# usbpsu2.net
KiCad netlist of a schematic drawn in EAGLE
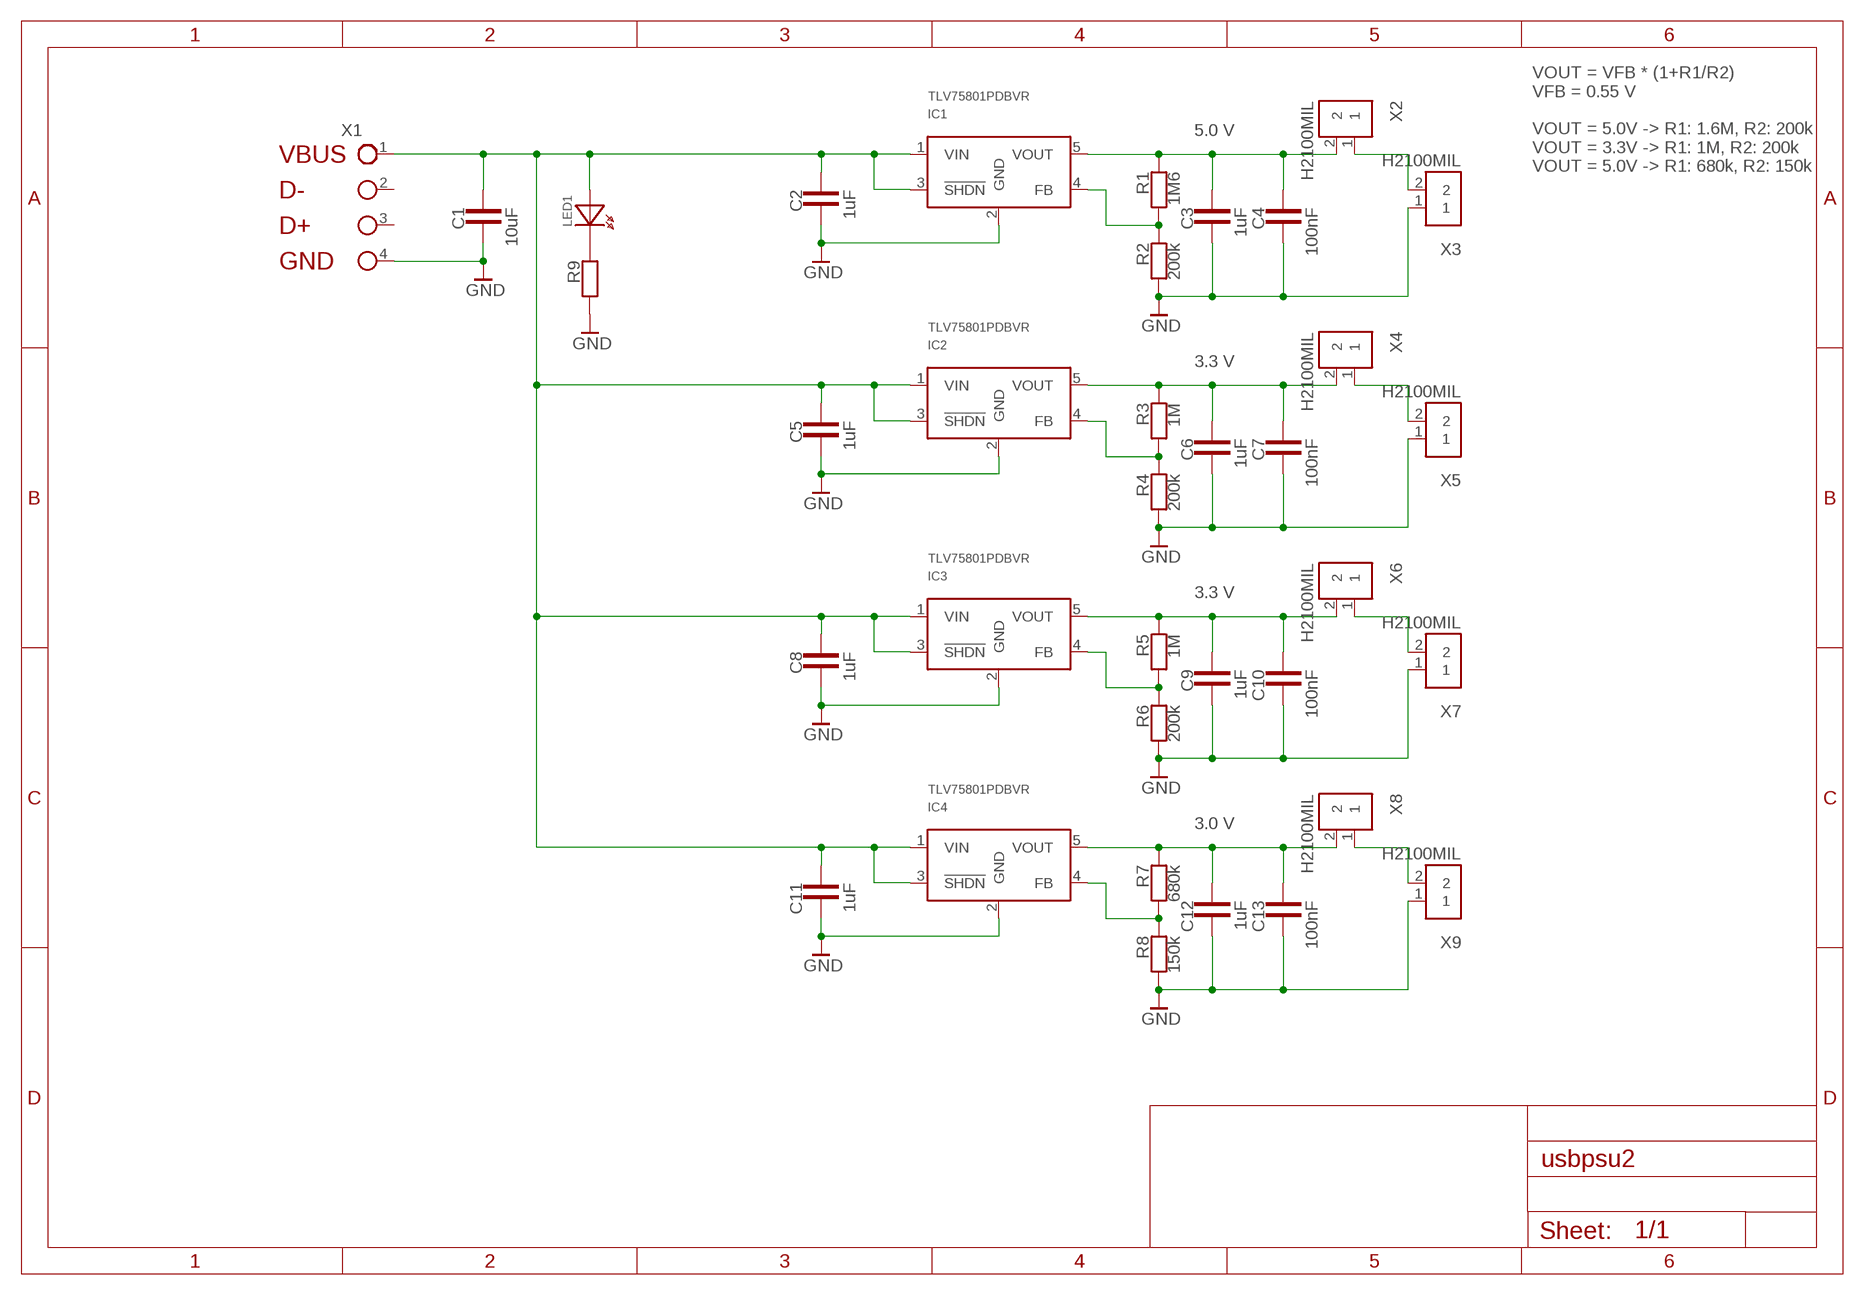
[diagram p0: schematic, sheet 1]

(export (version "E")
  (design (tool "Eeschema 10.0.6"))
  (components
    (comp (ref "C1")
      (value "10uF")
      (footprint "eagle-import:0805MIL")
      (libsource (lib "eagle-import") (part "C0805"))
    )
    (comp (ref "C2")
      (value "1uF")
      (footprint "eagle-import:0805MIL")
      (libsource (lib "eagle-import") (part "C0805"))
    )
    (comp (ref "C3")
      (value "1uF")
      (footprint "eagle-import:0805MIL")
      (libsource (lib "eagle-import") (part "C0805"))
    )
    (comp (ref "C4")
      (value "100nF")
      (footprint "eagle-import:0603MIL")
      (libsource (lib "eagle-import") (part "C0603"))
    )
    (comp (ref "C5")
      (value "1uF")
      (footprint "eagle-import:0805MIL")
      (libsource (lib "eagle-import") (part "C0805"))
    )
    (comp (ref "C6")
      (value "1uF")
      (footprint "eagle-import:0805MIL")
      (libsource (lib "eagle-import") (part "C0805"))
    )
    (comp (ref "C7")
      (value "100nF")
      (footprint "eagle-import:0603MIL")
      (libsource (lib "eagle-import") (part "C0603"))
    )
    (comp (ref "C8")
      (value "1uF")
      (footprint "eagle-import:0805MIL")
      (libsource (lib "eagle-import") (part "C0805"))
    )
    (comp (ref "C9")
      (value "1uF")
      (footprint "eagle-import:0805MIL")
      (libsource (lib "eagle-import") (part "C0805"))
    )
    (comp (ref "C10")
      (value "100nF")
      (footprint "eagle-import:0603MIL")
      (libsource (lib "eagle-import") (part "C0603"))
    )
    (comp (ref "C11")
      (value "1uF")
      (footprint "eagle-import:0805MIL")
      (libsource (lib "eagle-import") (part "C0805"))
    )
    (comp (ref "C12")
      (value "1uF")
      (footprint "eagle-import:0805MIL")
      (libsource (lib "eagle-import") (part "C0805"))
    )
    (comp (ref "C13")
      (value "100nF")
      (footprint "eagle-import:0603MIL")
      (libsource (lib "eagle-import") (part "C0603"))
    )
    (comp (ref "IC1")
      (value "TLV75801PDBVR")
      (footprint "eagle-import:SOT23-5_2")
      (libsource (lib "eagle-import") (part "TLV75801PDBVR"))
    )
    (comp (ref "IC2")
      (value "TLV75801PDBVR")
      (footprint "eagle-import:SOT23-5_2")
      (libsource (lib "eagle-import") (part "TLV75801PDBVR"))
    )
    (comp (ref "IC3")
      (value "TLV75801PDBVR")
      (footprint "eagle-import:SOT23-5_2")
      (libsource (lib "eagle-import") (part "TLV75801PDBVR"))
    )
    (comp (ref "IC4")
      (value "TLV75801PDBVR")
      (footprint "eagle-import:SOT23-5_2")
      (libsource (lib "eagle-import") (part "TLV75801PDBVR"))
    )
    (comp (ref "LED1")
      (value "LED0603")
      (footprint "eagle-import:0603MIL_POL")
      (libsource (lib "eagle-import") (part "LED0603"))
    )
    (comp (ref "R1")
      (value "1M6")
      (footprint "eagle-import:0603MIL")
      (libsource (lib "eagle-import") (part "R0603"))
    )
    (comp (ref "R2")
      (value "200k")
      (footprint "eagle-import:0603MIL")
      (libsource (lib "eagle-import") (part "R0603"))
    )
    (comp (ref "R3")
      (value "1M")
      (footprint "eagle-import:0603MIL")
      (libsource (lib "eagle-import") (part "R0603"))
    )
    (comp (ref "R4")
      (value "200k")
      (footprint "eagle-import:0603MIL")
      (libsource (lib "eagle-import") (part "R0603"))
    )
    (comp (ref "R5")
      (value "1M")
      (footprint "eagle-import:0603MIL")
      (libsource (lib "eagle-import") (part "R0603"))
    )
    (comp (ref "R6")
      (value "200k")
      (footprint "eagle-import:0603MIL")
      (libsource (lib "eagle-import") (part "R0603"))
    )
    (comp (ref "R7")
      (value "680k")
      (footprint "eagle-import:0603MIL")
      (libsource (lib "eagle-import") (part "R0603"))
    )
    (comp (ref "R8")
      (value "150k")
      (footprint "eagle-import:0603MIL")
      (libsource (lib "eagle-import") (part "R0603"))
    )
    (comp (ref "R9")
      (value "R0603")
      (footprint "eagle-import:0603MIL")
      (libsource (lib "eagle-import") (part "R0603"))
    )
    (comp (ref "X1")
      (value "H4USB")
      (footprint "eagle-import:HEADER4_100MIL")
      (libsource (lib "eagle-import") (part "H4USB"))
    )
    (comp (ref "X2")
      (value "H2100MIL")
      (footprint "eagle-import:HEADER2_100MIL")
      (libsource (lib "eagle-import") (part "H2100MIL"))
    )
    (comp (ref "X3")
      (value "H2100MIL")
      (footprint "eagle-import:HEADER2_100MIL")
      (libsource (lib "eagle-import") (part "H2100MIL"))
    )
    (comp (ref "X4")
      (value "H2100MIL")
      (footprint "eagle-import:HEADER2_100MIL")
      (libsource (lib "eagle-import") (part "H2100MIL"))
    )
    (comp (ref "X5")
      (value "H2100MIL")
      (footprint "eagle-import:HEADER2_100MIL")
      (libsource (lib "eagle-import") (part "H2100MIL"))
    )
    (comp (ref "X6")
      (value "H2100MIL")
      (footprint "eagle-import:HEADER2_100MIL")
      (libsource (lib "eagle-import") (part "H2100MIL"))
    )
    (comp (ref "X7")
      (value "H2100MIL")
      (footprint "eagle-import:HEADER2_100MIL")
      (libsource (lib "eagle-import") (part "H2100MIL"))
    )
    (comp (ref "X8")
      (value "H2100MIL")
      (footprint "eagle-import:HEADER2_100MIL")
      (libsource (lib "eagle-import") (part "H2100MIL"))
    )
    (comp (ref "X9")
      (value "H2100MIL")
      (footprint "eagle-import:HEADER2_100MIL")
      (libsource (lib "eagle-import") (part "H2100MIL"))
    )
  )
  (nets
    (net (code "1") (name "GND") (class "Default")
      (node (ref "C1") (pin "2") (pinfunction "2_2") (pintype "passive"))
      (node (ref "C10") (pin "2") (pinfunction "2_2") (pintype "passive"))
      (node (ref "C11") (pin "2") (pinfunction "2_2") (pintype "passive"))
      (node (ref "C12") (pin "2") (pinfunction "2_2") (pintype "passive"))
      (node (ref "C13") (pin "2") (pinfunction "2_2") (pintype "passive"))
      (node (ref "C2") (pin "2") (pinfunction "2_2") (pintype "passive"))
      (node (ref "C3") (pin "2") (pinfunction "2_2") (pintype "passive"))
      (node (ref "C4") (pin "2") (pinfunction "2_2") (pintype "passive"))
      (node (ref "C5") (pin "2") (pinfunction "2_2") (pintype "passive"))
      (node (ref "C6") (pin "2") (pinfunction "2_2") (pintype "passive"))
      (node (ref "C7") (pin "2") (pinfunction "2_2") (pintype "passive"))
      (node (ref "C8") (pin "2") (pinfunction "2_2") (pintype "passive"))
      (node (ref "C9") (pin "2") (pinfunction "2_2") (pintype "passive"))
      (node (ref "IC1") (pin "2") (pinfunction "GND_2") (pintype "bidirectional"))
      (node (ref "IC2") (pin "2") (pinfunction "GND_2") (pintype "bidirectional"))
      (node (ref "IC3") (pin "2") (pinfunction "GND_2") (pintype "bidirectional"))
      (node (ref "IC4") (pin "2") (pinfunction "GND_2") (pintype "bidirectional"))
      (node (ref "R2") (pin "2") (pinfunction "2_2") (pintype "passive"))
      (node (ref "R4") (pin "2") (pinfunction "2_2") (pintype "passive"))
      (node (ref "R6") (pin "2") (pinfunction "2_2") (pintype "passive"))
      (node (ref "R8") (pin "2") (pinfunction "2_2") (pintype "passive"))
      (node (ref "R9") (pin "2") (pinfunction "2_2") (pintype "passive"))
      (node (ref "X1") (pin "4") (pinfunction "GND_4") (pintype "bidirectional"))
      (node (ref "X3") (pin "1") (pinfunction "1_1") (pintype "bidirectional"))
      (node (ref "X5") (pin "1") (pinfunction "1_1") (pintype "bidirectional"))
      (node (ref "X7") (pin "1") (pinfunction "1_1") (pintype "bidirectional"))
      (node (ref "X9") (pin "1") (pinfunction "1_1") (pintype "bidirectional"))
    )
    (net (code "2") (name "Net-(IC1-FB)") (class "Default")
      (node (ref "IC1") (pin "4") (pinfunction "FB_4") (pintype "bidirectional"))
      (node (ref "R1") (pin "2") (pinfunction "2_2") (pintype "passive"))
      (node (ref "R2") (pin "1") (pinfunction "1_1") (pintype "passive"))
    )
    (net (code "3") (name "Net-(IC1-VIN)") (class "Default")
      (node (ref "C1") (pin "1") (pinfunction "1_1") (pintype "passive"))
      (node (ref "C11") (pin "1") (pinfunction "1_1") (pintype "passive"))
      (node (ref "C2") (pin "1") (pinfunction "1_1") (pintype "passive"))
      (node (ref "C5") (pin "1") (pinfunction "1_1") (pintype "passive"))
      (node (ref "C8") (pin "1") (pinfunction "1_1") (pintype "passive"))
      (node (ref "IC1") (pin "1") (pinfunction "VIN_1") (pintype "bidirectional"))
      (node (ref "IC1") (pin "3") (pinfunction "~{SHDN}_3") (pintype "bidirectional"))
      (node (ref "IC2") (pin "1") (pinfunction "VIN_1") (pintype "bidirectional"))
      (node (ref "IC2") (pin "3") (pinfunction "~{SHDN}_3") (pintype "bidirectional"))
      (node (ref "IC3") (pin "1") (pinfunction "VIN_1") (pintype "bidirectional"))
      (node (ref "IC3") (pin "3") (pinfunction "~{SHDN}_3") (pintype "bidirectional"))
      (node (ref "IC4") (pin "1") (pinfunction "VIN_1") (pintype "bidirectional"))
      (node (ref "IC4") (pin "3") (pinfunction "~{SHDN}_3") (pintype "bidirectional"))
      (node (ref "LED1") (pin "1") (pinfunction "A_1") (pintype "passive"))
      (node (ref "X1") (pin "1") (pinfunction "VBUS_1") (pintype "bidirectional"))
    )
    (net (code "4") (name "Net-(IC1-VOUT)") (class "Default")
      (node (ref "C3") (pin "1") (pinfunction "1_1") (pintype "passive"))
      (node (ref "C4") (pin "1") (pinfunction "1_1") (pintype "passive"))
      (node (ref "IC1") (pin "5") (pinfunction "VOUT_5") (pintype "bidirectional"))
      (node (ref "R1") (pin "1") (pinfunction "1_1") (pintype "passive"))
      (node (ref "X2") (pin "2") (pinfunction "2_2") (pintype "bidirectional"))
    )
    (net (code "5") (name "Net-(IC2-FB)") (class "Default")
      (node (ref "IC2") (pin "4") (pinfunction "FB_4") (pintype "bidirectional"))
      (node (ref "R3") (pin "2") (pinfunction "2_2") (pintype "passive"))
      (node (ref "R4") (pin "1") (pinfunction "1_1") (pintype "passive"))
    )
    (net (code "6") (name "Net-(IC2-VOUT)") (class "Default")
      (node (ref "C6") (pin "1") (pinfunction "1_1") (pintype "passive"))
      (node (ref "C7") (pin "1") (pinfunction "1_1") (pintype "passive"))
      (node (ref "IC2") (pin "5") (pinfunction "VOUT_5") (pintype "bidirectional"))
      (node (ref "R3") (pin "1") (pinfunction "1_1") (pintype "passive"))
      (node (ref "X4") (pin "2") (pinfunction "2_2") (pintype "bidirectional"))
    )
    (net (code "7") (name "Net-(IC3-FB)") (class "Default")
      (node (ref "IC3") (pin "4") (pinfunction "FB_4") (pintype "bidirectional"))
      (node (ref "R5") (pin "2") (pinfunction "2_2") (pintype "passive"))
      (node (ref "R6") (pin "1") (pinfunction "1_1") (pintype "passive"))
    )
    (net (code "8") (name "Net-(IC3-VOUT)") (class "Default")
      (node (ref "C10") (pin "1") (pinfunction "1_1") (pintype "passive"))
      (node (ref "C9") (pin "1") (pinfunction "1_1") (pintype "passive"))
      (node (ref "IC3") (pin "5") (pinfunction "VOUT_5") (pintype "bidirectional"))
      (node (ref "R5") (pin "1") (pinfunction "1_1") (pintype "passive"))
      (node (ref "X6") (pin "2") (pinfunction "2_2") (pintype "bidirectional"))
    )
    (net (code "9") (name "Net-(IC4-FB)") (class "Default")
      (node (ref "IC4") (pin "4") (pinfunction "FB_4") (pintype "bidirectional"))
      (node (ref "R7") (pin "2") (pinfunction "2_2") (pintype "passive"))
      (node (ref "R8") (pin "1") (pinfunction "1_1") (pintype "passive"))
    )
    (net (code "10") (name "Net-(IC4-VOUT)") (class "Default")
      (node (ref "C12") (pin "1") (pinfunction "1_1") (pintype "passive"))
      (node (ref "C13") (pin "1") (pinfunction "1_1") (pintype "passive"))
      (node (ref "IC4") (pin "5") (pinfunction "VOUT_5") (pintype "bidirectional"))
      (node (ref "R7") (pin "1") (pinfunction "1_1") (pintype "passive"))
      (node (ref "X8") (pin "2") (pinfunction "2_2") (pintype "bidirectional"))
    )
    (net (code "11") (name "Net-(LED1-K)") (class "Default")
      (node (ref "LED1") (pin "2") (pinfunction "K_2") (pintype "passive"))
      (node (ref "R9") (pin "1") (pinfunction "1_1") (pintype "passive"))
    )
    (net (code "12") (name "Net-(X2-Pad1)") (class "Default")
      (node (ref "X2") (pin "1") (pinfunction "1_1") (pintype "bidirectional"))
      (node (ref "X3") (pin "2") (pinfunction "2_2") (pintype "bidirectional"))
    )
    (net (code "13") (name "Net-(X4-Pad1)") (class "Default")
      (node (ref "X4") (pin "1") (pinfunction "1_1") (pintype "bidirectional"))
      (node (ref "X5") (pin "2") (pinfunction "2_2") (pintype "bidirectional"))
    )
    (net (code "14") (name "Net-(X6-Pad1)") (class "Default")
      (node (ref "X6") (pin "1") (pinfunction "1_1") (pintype "bidirectional"))
      (node (ref "X7") (pin "2") (pinfunction "2_2") (pintype "bidirectional"))
    )
    (net (code "15") (name "Net-(X8-Pad1)") (class "Default")
      (node (ref "X8") (pin "1") (pinfunction "1_1") (pintype "bidirectional"))
      (node (ref "X9") (pin "2") (pinfunction "2_2") (pintype "bidirectional"))
    )
    (net (code "16") (name "unconnected-(X1-D+-Pad3)") (class "Default")
      (node (ref "X1") (pin "3") (pinfunction "D+_3") (pintype "bidirectional"))
    )
    (net (code "17") (name "unconnected-(X1-D--Pad2)") (class "Default")
      (node (ref "X1") (pin "2") (pinfunction "D-_2") (pintype "bidirectional"))
    )
  )
)
